# sensor.net
KiCad netlist of a schematic drawn in EAGLE
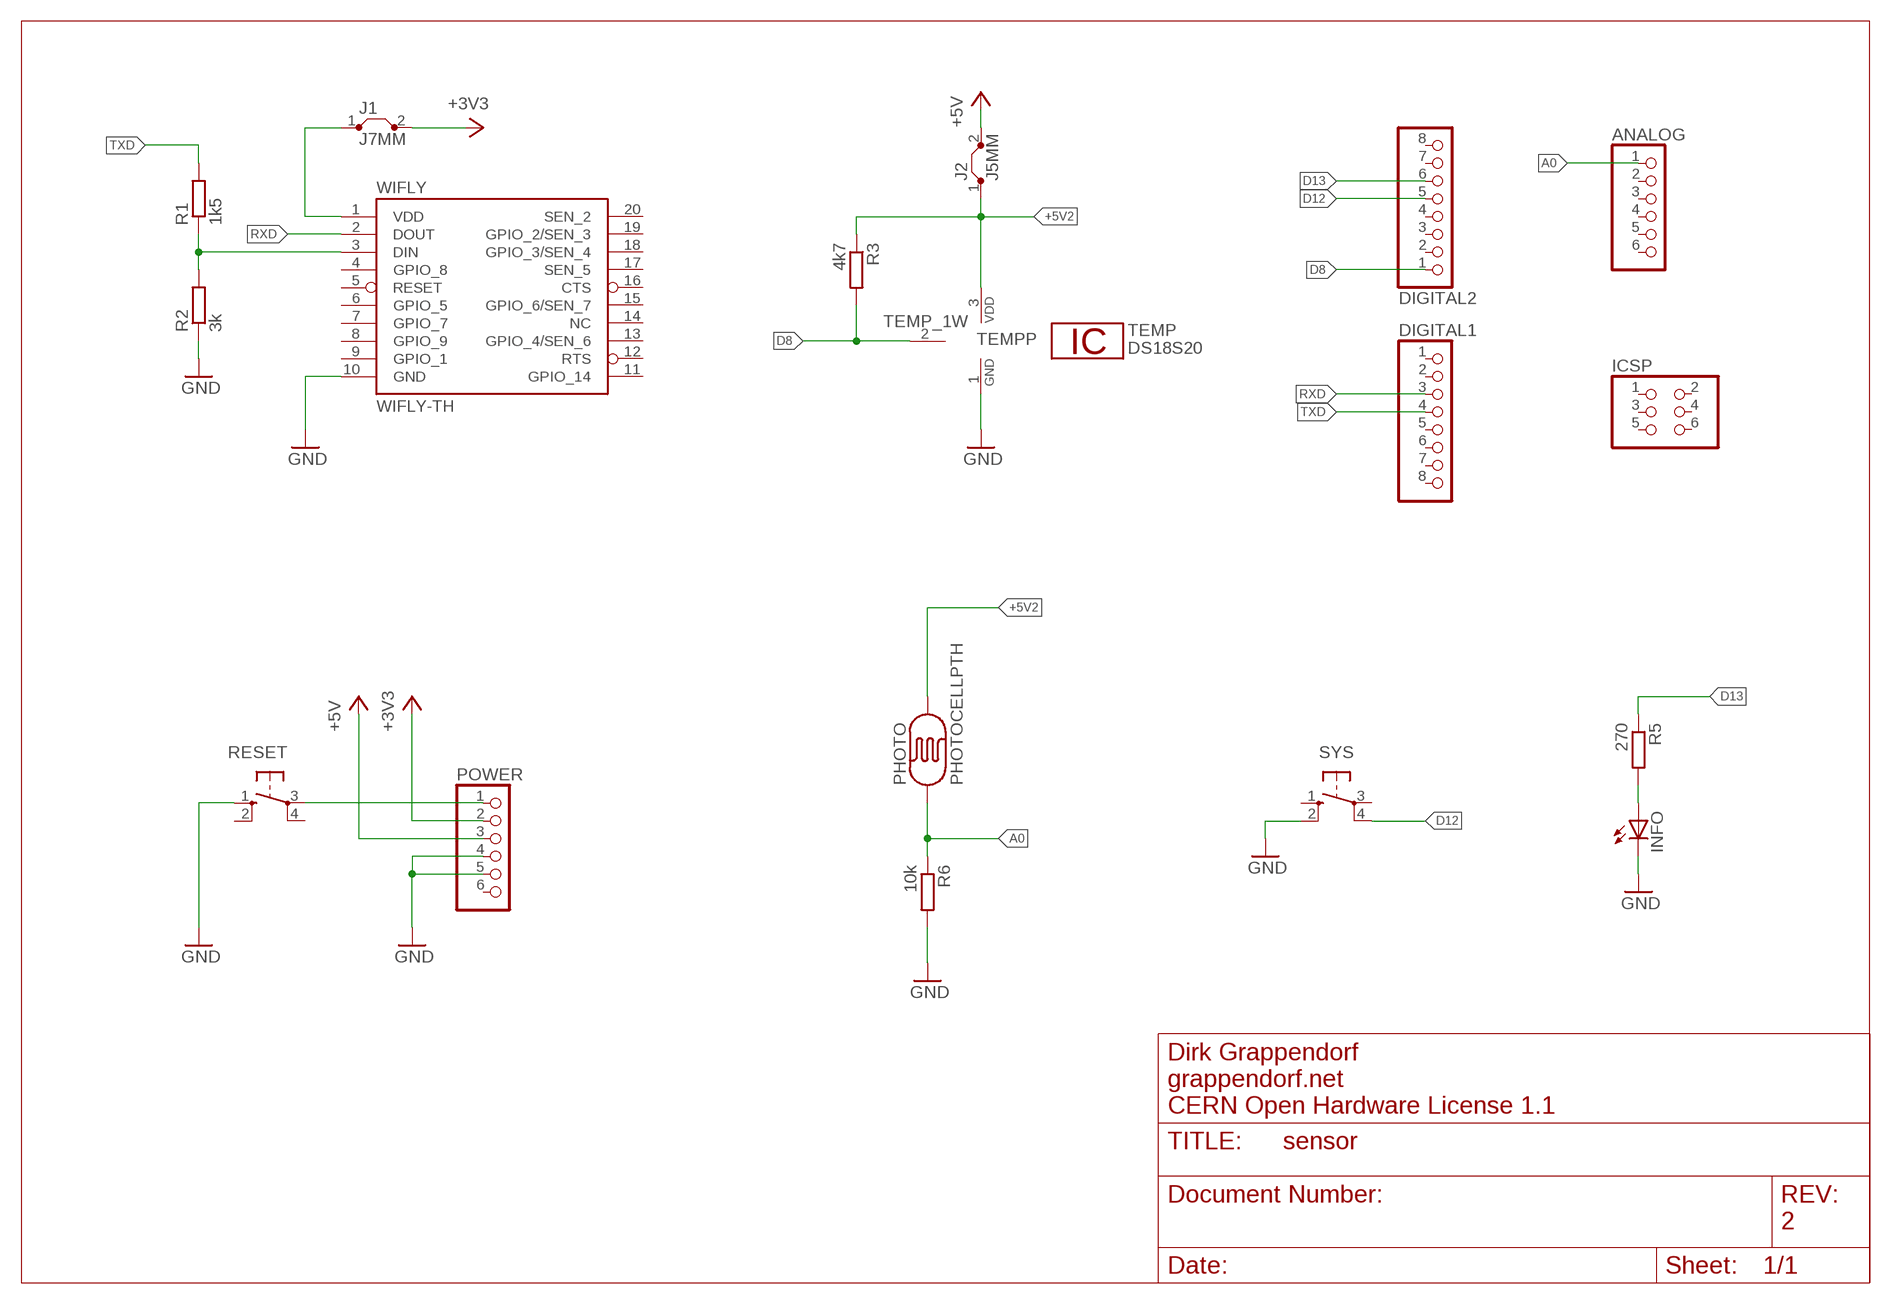
[diagram p0: schematic, sheet 1]

(export (version "E")
  (design (tool "Eeschema 10.0.6"))
  (components
    (comp (ref "ANALOG")
      (value "PINHD-1X6")
      (footprint "eagle-import:1X06")
      (libsource (lib "eagle-import") (part "PINHD-1X6"))
    )
    (comp (ref "DIGITAL1")
      (value "PINHD-1X8TH")
      (footprint "eagle-import:1X08-TH")
      (libsource (lib "eagle-import") (part "PINHD-1X8TH"))
    )
    (comp (ref "DIGITAL2")
      (value "PINHD-1X8_2.54")
      (footprint "eagle-import:1X08")
      (libsource (lib "eagle-import") (part "PINHD-1X8_2.54"))
    )
    (comp (ref "ICSP")
      (value "PINHD-2X3")
      (footprint "eagle-import:2X03")
      (libsource (lib "eagle-import") (part "PINHD-2X3"))
    )
    (comp (ref "INFO")
      (value "LED3MM")
      (footprint "eagle-import:LED3MM")
      (libsource (lib "eagle-import") (part "LED3MM"))
    )
    (comp (ref "J1")
      (value "J7MM")
      (footprint "eagle-import:07")
      (libsource (lib "eagle-import") (part "J7MM"))
    )
    (comp (ref "J2")
      (value "J5MM")
      (footprint "eagle-import:05")
      (libsource (lib "eagle-import") (part "J5MM"))
    )
    (comp (ref "PHOTO")
      (value "PHOTOCELLPTH")
      (footprint "eagle-import:PHOTOCELL")
      (libsource (lib "eagle-import") (part "PHOTOCELLPTH"))
    )
    (comp (ref "POWER")
      (value "PINHD-1X6_2.54")
      (footprint "eagle-import:1X06")
      (libsource (lib "eagle-import") (part "PINHD-1X6_2.54"))
    )
    (comp (ref "R1")
      (value "1k5")
      (footprint "eagle-import:0204_7")
      (libsource (lib "eagle-import") (part "R-EU_0204/7"))
    )
    (comp (ref "R2")
      (value "3k")
      (footprint "eagle-import:0204_7")
      (libsource (lib "eagle-import") (part "R-EU_0204/7"))
    )
    (comp (ref "R3")
      (value "4k7")
      (footprint "eagle-import:0204_7")
      (libsource (lib "eagle-import") (part "R-EU_0204/7"))
    )
    (comp (ref "R5")
      (value "270")
      (footprint "eagle-import:0204_7")
      (libsource (lib "eagle-import") (part "R-EU_0204/7"))
    )
    (comp (ref "R6")
      (value "10k")
      (footprint "eagle-import:0204_7")
      (libsource (lib "eagle-import") (part "R-EU_0204/7"))
    )
    (comp (ref "RESET")
      (value "10-XX")
      (footprint "eagle-import:B3F-10XX")
      (libsource (lib "eagle-import") (part "10-XX"))
    )
    (comp (ref "SYS")
      (value "10-XX")
      (footprint "eagle-import:B3F-10XX")
      (libsource (lib "eagle-import") (part "10-XX"))
    )
    (comp (ref "TEMP")
      (value "DS18S20")
      (footprint "eagle-import:TO92-")
      (libsource (lib "eagle-import") (part "DS18S20"))
    )
    (comp (ref "WIFLY")
      (value "WIFLY-TH")
      (footprint "eagle-import:WIFLY-TH")
      (libsource (lib "eagle-import") (part "WIFLY-TH"))
    )
  )
  (nets
    (net (code "1") (name "+3V3") (class "Default")
      (node (ref "J1") (pin "2") (pinfunction "2_2") (pintype "passive"))
      (node (ref "POWER") (pin "2") (pinfunction "2_2") (pintype "passive"))
    )
    (net (code "2") (name "+5V") (class "Default")
      (node (ref "J2") (pin "2") (pinfunction "2_2") (pintype "passive"))
      (node (ref "POWER") (pin "3") (pinfunction "3_3") (pintype "passive"))
    )
    (net (code "3") (name "+5V2") (class "Default")
      (node (ref "J2") (pin "1") (pinfunction "1_1") (pintype "passive"))
      (node (ref "PHOTO") (pin "2") (pinfunction "P$2_2") (pintype "bidirectional"))
      (node (ref "R3") (pin "1") (pinfunction "1_1") (pintype "passive"))
      (node (ref "TEMP") (pin "3") (pinfunction "VDD_3") (pintype "power_in"))
    )
    (net (code "4") (name "A0") (class "Default")
      (node (ref "ANALOG") (pin "1") (pinfunction "1_1") (pintype "passive"))
      (node (ref "PHOTO") (pin "1") (pinfunction "P$1_1") (pintype "bidirectional"))
      (node (ref "R6") (pin "1") (pinfunction "1_1") (pintype "passive"))
    )
    (net (code "5") (name "D8") (class "Default")
      (node (ref "DIGITAL2") (pin "1") (pinfunction "1_1") (pintype "passive"))
      (node (ref "R3") (pin "2") (pinfunction "2_2") (pintype "passive"))
      (node (ref "TEMP") (pin "2") (pinfunction "1W_2") (pintype "power_in"))
    )
    (net (code "6") (name "D12") (class "Default")
      (node (ref "DIGITAL2") (pin "5") (pinfunction "5_5") (pintype "passive"))
      (node (ref "SYS") (pin "4") (pinfunction "P1_4") (pintype "passive"))
    )
    (net (code "7") (name "D13") (class "Default")
      (node (ref "DIGITAL2") (pin "6") (pinfunction "6_6") (pintype "passive"))
      (node (ref "R5") (pin "1") (pinfunction "1_1") (pintype "passive"))
    )
    (net (code "8") (name "GND") (class "Default")
      (node (ref "INFO") (pin "K") (pinfunction "C_K") (pintype "passive"))
      (node (ref "POWER") (pin "4") (pinfunction "4_4") (pintype "passive"))
      (node (ref "POWER") (pin "5") (pinfunction "5_5") (pintype "passive"))
      (node (ref "R2") (pin "1") (pinfunction "1_1") (pintype "passive"))
      (node (ref "R6") (pin "2") (pinfunction "2_2") (pintype "passive"))
      (node (ref "RESET") (pin "1") (pinfunction "S_1") (pintype "passive"))
      (node (ref "SYS") (pin "2") (pinfunction "S1_2") (pintype "passive"))
      (node (ref "TEMP") (pin "1") (pinfunction "GND_1") (pintype "power_in"))
      (node (ref "WIFLY") (pin "10") (pinfunction "GND_10") (pintype "power_in"))
    )
    (net (code "9") (name "Net-(INFO-PadA)") (class "Default")
      (node (ref "INFO") (pin "A") (pinfunction "A_A") (pintype "passive"))
      (node (ref "R5") (pin "2") (pinfunction "2_2") (pintype "passive"))
    )
    (net (code "10") (name "Net-(RESET-P)") (class "Default")
      (node (ref "POWER") (pin "1") (pinfunction "1_1") (pintype "passive"))
      (node (ref "RESET") (pin "3") (pinfunction "P_3") (pintype "passive"))
    )
    (net (code "11") (name "Net-(WIFLY-DIN)") (class "Default")
      (node (ref "R1") (pin "1") (pinfunction "1_1") (pintype "passive"))
      (node (ref "R2") (pin "2") (pinfunction "2_2") (pintype "passive"))
      (node (ref "WIFLY") (pin "3") (pinfunction "DIN_3") (pintype "input"))
    )
    (net (code "12") (name "Net-(WIFLY-VDD)") (class "Default")
      (node (ref "J1") (pin "1") (pinfunction "1_1") (pintype "passive"))
      (node (ref "WIFLY") (pin "1") (pinfunction "VDD_1") (pintype "power_in"))
    )
    (net (code "13") (name "RXD") (class "Default")
      (node (ref "DIGITAL1") (pin "3") (pinfunction "3_3") (pintype "passive"))
      (node (ref "WIFLY") (pin "2") (pinfunction "DOUT_2") (pintype "output"))
    )
    (net (code "14") (name "TXD") (class "Default")
      (node (ref "DIGITAL1") (pin "4") (pinfunction "4_4") (pintype "passive"))
      (node (ref "R1") (pin "2") (pinfunction "2_2") (pintype "passive"))
    )
    (net (code "15") (name "unconnected-(ANALOG-Pad2)") (class "Default")
      (node (ref "ANALOG") (pin "2") (pinfunction "2_2") (pintype "passive"))
    )
    (net (code "16") (name "unconnected-(ANALOG-Pad3)") (class "Default")
      (node (ref "ANALOG") (pin "3") (pinfunction "3_3") (pintype "passive"))
    )
    (net (code "17") (name "unconnected-(ANALOG-Pad4)") (class "Default")
      (node (ref "ANALOG") (pin "4") (pinfunction "4_4") (pintype "passive"))
    )
    (net (code "18") (name "unconnected-(ANALOG-Pad5)") (class "Default")
      (node (ref "ANALOG") (pin "5") (pinfunction "5_5") (pintype "passive"))
    )
    (net (code "19") (name "unconnected-(ANALOG-Pad6)") (class "Default")
      (node (ref "ANALOG") (pin "6") (pinfunction "6_6") (pintype "passive"))
    )
    (net (code "20") (name "unconnected-(DIGITAL1-Pad1)") (class "Default")
      (node (ref "DIGITAL1") (pin "1") (pinfunction "1_1") (pintype "passive"))
    )
    (net (code "21") (name "unconnected-(DIGITAL1-Pad2)") (class "Default")
      (node (ref "DIGITAL1") (pin "2") (pinfunction "2_2") (pintype "passive"))
    )
    (net (code "22") (name "unconnected-(DIGITAL1-Pad5)") (class "Default")
      (node (ref "DIGITAL1") (pin "5") (pinfunction "5_5") (pintype "passive"))
    )
    (net (code "23") (name "unconnected-(DIGITAL1-Pad6)") (class "Default")
      (node (ref "DIGITAL1") (pin "6") (pinfunction "6_6") (pintype "passive"))
    )
    (net (code "24") (name "unconnected-(DIGITAL1-Pad7)") (class "Default")
      (node (ref "DIGITAL1") (pin "7") (pinfunction "7_7") (pintype "passive"))
    )
    (net (code "25") (name "unconnected-(DIGITAL1-Pad8)") (class "Default")
      (node (ref "DIGITAL1") (pin "8") (pinfunction "8_8") (pintype "passive"))
    )
    (net (code "26") (name "unconnected-(DIGITAL2-Pad2)") (class "Default")
      (node (ref "DIGITAL2") (pin "2") (pinfunction "2_2") (pintype "passive"))
    )
    (net (code "27") (name "unconnected-(DIGITAL2-Pad3)") (class "Default")
      (node (ref "DIGITAL2") (pin "3") (pinfunction "3_3") (pintype "passive"))
    )
    (net (code "28") (name "unconnected-(DIGITAL2-Pad4)") (class "Default")
      (node (ref "DIGITAL2") (pin "4") (pinfunction "4_4") (pintype "passive"))
    )
    (net (code "29") (name "unconnected-(DIGITAL2-Pad7)") (class "Default")
      (node (ref "DIGITAL2") (pin "7") (pinfunction "7_7") (pintype "passive"))
    )
    (net (code "30") (name "unconnected-(DIGITAL2-Pad8)") (class "Default")
      (node (ref "DIGITAL2") (pin "8") (pinfunction "8_8") (pintype "passive"))
    )
    (net (code "31") (name "unconnected-(ICSP-Pad1)") (class "Default")
      (node (ref "ICSP") (pin "1") (pinfunction "1_1") (pintype "passive"))
    )
    (net (code "32") (name "unconnected-(ICSP-Pad2)") (class "Default")
      (node (ref "ICSP") (pin "2") (pinfunction "2_2") (pintype "passive"))
    )
    (net (code "33") (name "unconnected-(ICSP-Pad3)") (class "Default")
      (node (ref "ICSP") (pin "3") (pinfunction "3_3") (pintype "passive"))
    )
    (net (code "34") (name "unconnected-(ICSP-Pad4)") (class "Default")
      (node (ref "ICSP") (pin "4") (pinfunction "4_4") (pintype "passive"))
    )
    (net (code "35") (name "unconnected-(ICSP-Pad5)") (class "Default")
      (node (ref "ICSP") (pin "5") (pinfunction "5_5") (pintype "passive"))
    )
    (net (code "36") (name "unconnected-(ICSP-Pad6)") (class "Default")
      (node (ref "ICSP") (pin "6") (pinfunction "6_6") (pintype "passive"))
    )
    (net (code "37") (name "unconnected-(POWER-Pad6)") (class "Default")
      (node (ref "POWER") (pin "6") (pinfunction "6_6") (pintype "passive"))
    )
    (net (code "38") (name "unconnected-(RESET-P1-Pad4)") (class "Default")
      (node (ref "RESET") (pin "4") (pinfunction "P1_4") (pintype "passive"))
    )
    (net (code "39") (name "unconnected-(RESET-S1-Pad2)") (class "Default")
      (node (ref "RESET") (pin "2") (pinfunction "S1_2") (pintype "passive"))
    )
    (net (code "40") (name "unconnected-(SYS-P-Pad3)") (class "Default")
      (node (ref "SYS") (pin "3") (pinfunction "P_3") (pintype "passive"))
    )
    (net (code "41") (name "unconnected-(SYS-S-Pad1)") (class "Default")
      (node (ref "SYS") (pin "1") (pinfunction "S_1") (pintype "passive"))
    )
    (net (code "42") (name "unconnected-(WIFLY-CTS-Pad16)") (class "Default")
      (node (ref "WIFLY") (pin "16") (pinfunction "CTS_16") (pintype "input"))
    )
    (net (code "43") (name "unconnected-(WIFLY-GPIO_1-Pad9)") (class "Default")
      (node (ref "WIFLY") (pin "9") (pinfunction "GPIO_1_9") (pintype "bidirectional"))
    )
    (net (code "44") (name "unconnected-(WIFLY-GPIO_2{slash}SEN_3-Pad19)") (class "Default")
      (node (ref "WIFLY") (pin "19") (pinfunction "GPIO_2/SEN_3_19") (pintype "bidirectional"))
    )
    (net (code "45") (name "unconnected-(WIFLY-GPIO_3{slash}SEN_4-Pad18)") (class "Default")
      (node (ref "WIFLY") (pin "18") (pinfunction "GPIO_3/SEN_4_18") (pintype "bidirectional"))
    )
    (net (code "46") (name "unconnected-(WIFLY-GPIO_4{slash}SEN_6-Pad13)") (class "Default")
      (node (ref "WIFLY") (pin "13") (pinfunction "GPIO_4/SEN_6_13") (pintype "bidirectional"))
    )
    (net (code "47") (name "unconnected-(WIFLY-GPIO_5-Pad6)") (class "Default")
      (node (ref "WIFLY") (pin "6") (pinfunction "GPIO_5_6") (pintype "bidirectional"))
    )
    (net (code "48") (name "unconnected-(WIFLY-GPIO_6{slash}SEN_7-Pad15)") (class "Default")
      (node (ref "WIFLY") (pin "15") (pinfunction "GPIO_6/SEN_7_15") (pintype "bidirectional"))
    )
    (net (code "49") (name "unconnected-(WIFLY-GPIO_7-Pad7)") (class "Default")
      (node (ref "WIFLY") (pin "7") (pinfunction "GPIO_7_7") (pintype "bidirectional"))
    )
    (net (code "50") (name "unconnected-(WIFLY-GPIO_8-Pad4)") (class "Default")
      (node (ref "WIFLY") (pin "4") (pinfunction "GPIO_8_4") (pintype "bidirectional"))
    )
    (net (code "51") (name "unconnected-(WIFLY-GPIO_9-Pad8)") (class "Default")
      (node (ref "WIFLY") (pin "8") (pinfunction "GPIO_9_8") (pintype "bidirectional"))
    )
    (net (code "52") (name "unconnected-(WIFLY-GPIO_14-Pad11)") (class "Default")
      (node (ref "WIFLY") (pin "11") (pinfunction "GPIO_14_11") (pintype "bidirectional"))
    )
    (net (code "53") (name "unconnected-(WIFLY-NC-Pad14)") (class "Default")
      (node (ref "WIFLY") (pin "14") (pinfunction "NC_14") (pintype "bidirectional"))
    )
    (net (code "54") (name "unconnected-(WIFLY-RESET-Pad5)") (class "Default")
      (node (ref "WIFLY") (pin "5") (pinfunction "RESET_5") (pintype "input"))
    )
    (net (code "55") (name "unconnected-(WIFLY-RTS-Pad12)") (class "Default")
      (node (ref "WIFLY") (pin "12") (pinfunction "RTS_12") (pintype "output"))
    )
    (net (code "56") (name "unconnected-(WIFLY-SEN_2-Pad20)") (class "Default")
      (node (ref "WIFLY") (pin "20") (pinfunction "SEN_2_20") (pintype "bidirectional"))
    )
    (net (code "57") (name "unconnected-(WIFLY-SEN_5-Pad17)") (class "Default")
      (node (ref "WIFLY") (pin "17") (pinfunction "SEN_5_17") (pintype "bidirectional"))
    )
  )
)
